# MB_RELAY.net
KiCad netlist of a schematic drawn in Altium Designer
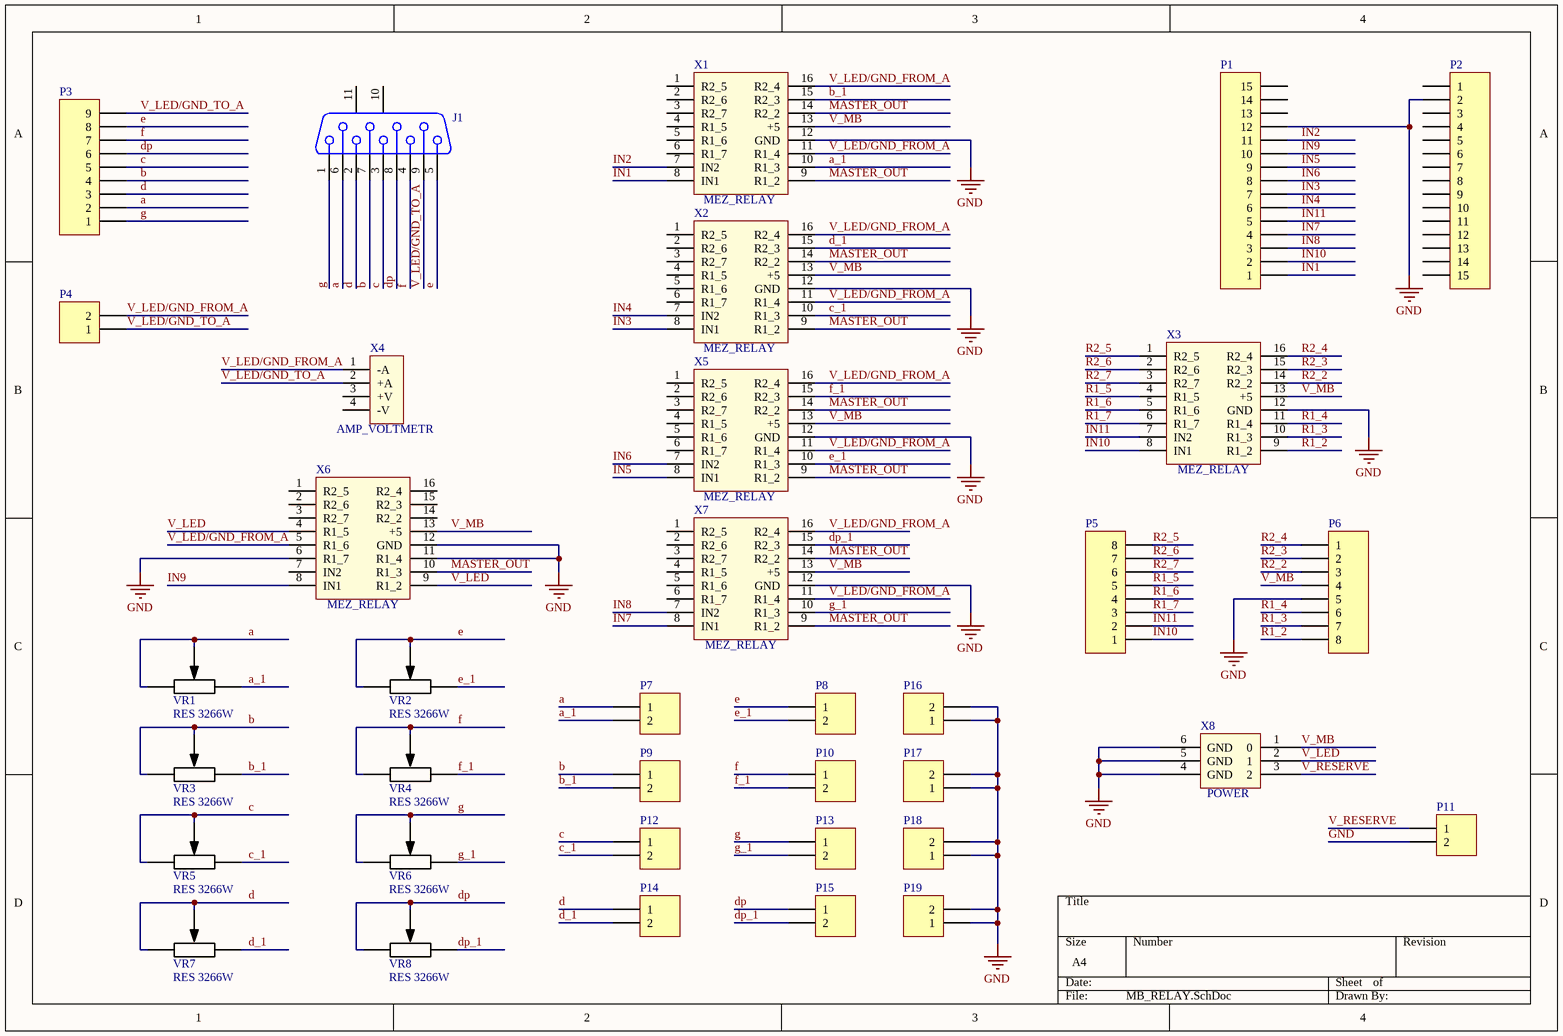
[diagram p0: MB_RELAY.SchDoc]

(export (version "E")
  (design (tool "Eeschema 10.0.6"))
  (components
    (comp (ref "J1")
      (value "D Connector 9")
      (footprint "DSUB1.385-2H9")
      (description "Receptacle Assembly, 9 Position, Right Angle")
      (fields (field (name "PUBLISHER") "Altium Limited"))
      (libsource (lib "Miscellaneous Connectors") (part "D Connector 9"))
    )
    (comp (ref "P1")
      (value "Header 15")
      (footprint "HDR1X15")
      (description "Header, 15-Pin")
      (fields (field (name "PUBLISHER") "Altium Limited"))
      (libsource (lib "Miscellaneous Connectors") (part "Header 15"))
    )
    (comp (ref "P2")
      (value "Header 15")
      (footprint "HDR1X15")
      (description "Header, 15-Pin")
      (fields (field (name "PUBLISHER") "Altium Limited"))
      (libsource (lib "") (part "Header 15_1"))
    )
    (comp (ref "P3")
      (value "Header 9")
      (footprint "HDR1X9")
      (description "Header, 9-Pin")
      (fields (field (name "PUBLISHER") "Altium Limited"))
      (libsource (lib "Miscellaneous Connectors") (part "Header 9"))
    )
    (comp (ref "P4")
      (value "Header 2")
      (footprint "HDR1X2")
      (description "Header, 2-Pin")
      (fields (field (name "PUBLISHER") "Altium Limited"))
      (libsource (lib "Miscellaneous Connectors") (part "Header 2"))
    )
    (comp (ref "P5")
      (value "Header 8")
      (footprint "HDR1X8")
      (description "Header, 8-Pin")
      (fields (field (name "PUBLISHER") "Altium Limited"))
      (libsource (lib "") (part "Header 8_1"))
    )
    (comp (ref "P6")
      (value "Header 8")
      (footprint "HDR1X8")
      (description "Header, 8-Pin")
      (fields (field (name "PUBLISHER") "Altium Limited"))
      (libsource (lib "Miscellaneous Connectors") (part "Header 8"))
    )
    (comp (ref "P7")
      (value "Header 2")
      (footprint "HDR1X2")
      (description "Header, 2-Pin")
      (fields (field (name "PUBLISHER") "Altium Limited"))
      (libsource (lib "") (part "Header 2_1"))
    )
    (comp (ref "P8")
      (value "GND")
      (footprint "HDR1X2")
      (description "Header, 2-Pin")
      (fields (field (name "PUBLISHER") "Altium Limited"))
      (libsource (lib "") (part "Header 2_1"))
    )
    (comp (ref "P9")
      (value "Header 2")
      (footprint "HDR1X2")
      (description "Header, 2-Pin")
      (fields (field (name "PUBLISHER") "Altium Limited"))
      (libsource (lib "") (part "Header 2_1"))
    )
    (comp (ref "P10")
      (value "GND")
      (footprint "HDR1X2")
      (description "Header, 2-Pin")
      (fields (field (name "PUBLISHER") "Altium Limited"))
      (libsource (lib "") (part "Header 2_1"))
    )
    (comp (ref "P11")
      (value "Header 2")
      (footprint "HDR1X2")
      (description "Header, 2-Pin")
      (fields (field (name "PUBLISHER") "Altium Limited"))
      (libsource (lib "") (part "Header 2_1"))
    )
    (comp (ref "P12")
      (value "Header 2")
      (footprint "HDR1X2")
      (description "Header, 2-Pin")
      (fields (field (name "PUBLISHER") "Altium Limited"))
      (libsource (lib "") (part "Header 2_1"))
    )
    (comp (ref "P13")
      (value "GND")
      (footprint "HDR1X2")
      (description "Header, 2-Pin")
      (fields (field (name "PUBLISHER") "Altium Limited"))
      (libsource (lib "") (part "Header 2_1"))
    )
    (comp (ref "P14")
      (value "Header 2")
      (footprint "HDR1X2")
      (description "Header, 2-Pin")
      (fields (field (name "PUBLISHER") "Altium Limited"))
      (libsource (lib "") (part "Header 2_1"))
    )
    (comp (ref "P15")
      (value "GND")
      (footprint "HDR1X2")
      (description "Header, 2-Pin")
      (fields (field (name "PUBLISHER") "Altium Limited"))
      (libsource (lib "") (part "Header 2_1"))
    )
    (comp (ref "P16")
      (value "GND")
      (footprint "HDR1X2")
      (description "Header, 2-Pin")
      (fields (field (name "PUBLISHER") "Altium Limited"))
      (libsource (lib "Miscellaneous Connectors") (part "Header 2"))
    )
    (comp (ref "P17")
      (value "GND")
      (footprint "HDR1X2")
      (description "Header, 2-Pin")
      (fields (field (name "PUBLISHER") "Altium Limited"))
      (libsource (lib "Miscellaneous Connectors") (part "Header 2"))
    )
    (comp (ref "P18")
      (value "GND")
      (footprint "HDR1X2")
      (description "Header, 2-Pin")
      (fields (field (name "PUBLISHER") "Altium Limited"))
      (libsource (lib "Miscellaneous Connectors") (part "Header 2"))
    )
    (comp (ref "P19")
      (value "GND")
      (footprint "HDR1X2")
      (description "Header, 2-Pin")
      (fields (field (name "PUBLISHER") "Altium Limited"))
      (libsource (lib "Miscellaneous Connectors") (part "Header 2"))
    )
    (comp (ref "VR1")
      (value "RES 3266W")
      (footprint "aab_Passive:RES 3266W")
      (libsource (lib "aab_Schlib") (part "RES 3266W"))
    )
    (comp (ref "VR2")
      (value "RES 3266W")
      (footprint "aab_Passive:RES 3266W")
      (libsource (lib "aab_Schlib") (part "RES 3266W"))
    )
    (comp (ref "VR3")
      (value "RES 3266W")
      (footprint "aab_Passive:RES 3266W")
      (libsource (lib "aab_Schlib") (part "RES 3266W"))
    )
    (comp (ref "VR4")
      (value "RES 3266W")
      (footprint "aab_Passive:RES 3266W")
      (libsource (lib "aab_Schlib") (part "RES 3266W"))
    )
    (comp (ref "VR5")
      (value "RES 3266W")
      (footprint "aab_Passive:RES 3266W")
      (libsource (lib "aab_Schlib") (part "RES 3266W"))
    )
    (comp (ref "VR6")
      (value "RES 3266W")
      (footprint "aab_Passive:RES 3266W")
      (libsource (lib "aab_Schlib") (part "RES 3266W"))
    )
    (comp (ref "VR7")
      (value "RES 3266W")
      (footprint "aab_Passive:RES 3266W")
      (libsource (lib "aab_Schlib") (part "RES 3266W"))
    )
    (comp (ref "VR8")
      (value "RES 3266W")
      (footprint "aab_Passive:RES 3266W")
      (libsource (lib "aab_Schlib") (part "RES 3266W"))
    )
    (comp (ref "X1")
      (value "MEZ_RELAY")
      (footprint "MEZ_RELAY")
      (libsource (lib "msp_SchLib") (part "MEZ_RELAY"))
    )
    (comp (ref "X2")
      (value "MEZ_RELAY")
      (footprint "MEZ_RELAY")
      (libsource (lib "msp_SchLib") (part "MEZ_RELAY"))
    )
    (comp (ref "X3")
      (value "MEZ_RELAY")
      (footprint "MEZ_RELAY")
      (libsource (lib "msp_SchLib") (part "MEZ_RELAY"))
    )
    (comp (ref "X4")
      (value "AMP_VOLTMETR")
      (footprint "vpl_Passive:AMP_VOLTMETER")
      (libsource (lib "msp_SchLib") (part "AMP_VOLTMETR"))
    )
    (comp (ref "X5")
      (value "MEZ_RELAY")
      (footprint "MEZ_RELAY")
      (libsource (lib "msp_SchLib") (part "MEZ_RELAY"))
    )
    (comp (ref "X6")
      (value "MEZ_RELAY")
      (footprint "MEZ_RELAY")
      (libsource (lib "msp_SchLib") (part "MEZ_RELAY"))
    )
    (comp (ref "X7")
      (value "MEZ_RELAY")
      (footprint "MEZ_RELAY")
      (libsource (lib "msp_SchLib") (part "MEZ_RELAY"))
    )
    (comp (ref "X8")
      (value "POWER")
      (footprint "vpl_Passive:POWER")
      (libsource (lib "msp_SchLib") (part "POWER"))
    )
  )
  (nets
    (net (code "1") (name "/IN1") (class "Default")
      (node (ref "P1") (pin "1") (pinfunction "1_1") (pintype "passive"))
      (node (ref "X1") (pin "8") (pinfunction "IN1_8") (pintype "passive"))
    )
    (net (code "2") (name "/IN2") (class "Default")
      (node (ref "P1") (pin "11") (pinfunction "11_11") (pintype "passive"))
      (node (ref "X1") (pin "7") (pinfunction "IN2_7") (pintype "passive"))
    )
    (net (code "3") (name "/IN3") (class "Default")
      (node (ref "P1") (pin "7") (pinfunction "7_7") (pintype "passive"))
      (node (ref "X2") (pin "8") (pinfunction "IN1_8") (pintype "passive"))
    )
    (net (code "4") (name "/IN4") (class "Default")
      (node (ref "P1") (pin "6") (pinfunction "6_6") (pintype "passive"))
      (node (ref "X2") (pin "7") (pinfunction "IN2_7") (pintype "passive"))
    )
    (net (code "5") (name "/IN5") (class "Default")
      (node (ref "P1") (pin "9") (pinfunction "9_9") (pintype "passive"))
      (node (ref "X5") (pin "8") (pinfunction "IN1_8") (pintype "passive"))
    )
    (net (code "6") (name "/IN6") (class "Default")
      (node (ref "P1") (pin "8") (pinfunction "8_8") (pintype "passive"))
      (node (ref "X5") (pin "7") (pinfunction "IN2_7") (pintype "passive"))
    )
    (net (code "7") (name "/IN7") (class "Default")
      (node (ref "P1") (pin "4") (pinfunction "4_4") (pintype "passive"))
      (node (ref "X7") (pin "8") (pinfunction "IN1_8") (pintype "passive"))
    )
    (net (code "8") (name "/IN8") (class "Default")
      (node (ref "P1") (pin "3") (pinfunction "3_3") (pintype "passive"))
      (node (ref "X7") (pin "7") (pinfunction "IN2_7") (pintype "passive"))
    )
    (net (code "9") (name "/IN9") (class "Default")
      (node (ref "P1") (pin "10") (pinfunction "10_10") (pintype "passive"))
      (node (ref "X6") (pin "8") (pinfunction "IN1_8") (pintype "passive"))
    )
    (net (code "10") (name "/IN10") (class "Default")
      (node (ref "P1") (pin "2") (pinfunction "2_2") (pintype "passive"))
      (node (ref "P5") (pin "1") (pinfunction "1_1") (pintype "passive"))
      (node (ref "X3") (pin "8") (pinfunction "IN1_8") (pintype "passive"))
    )
    (net (code "11") (name "/IN11") (class "Default")
      (node (ref "P1") (pin "5") (pinfunction "5_5") (pintype "passive"))
      (node (ref "P5") (pin "2") (pinfunction "2_2") (pintype "passive"))
      (node (ref "X3") (pin "7") (pinfunction "IN2_7") (pintype "passive"))
    )
    (net (code "12") (name "/MASTER_OUT") (class "Default")
      (node (ref "X1") (pin "14") (pinfunction "R2_2_14") (pintype "passive"))
      (node (ref "X1") (pin "9") (pinfunction "R1_2_9") (pintype "passive"))
      (node (ref "X2") (pin "14") (pinfunction "R2_2_14") (pintype "passive"))
      (node (ref "X2") (pin "9") (pinfunction "R1_2_9") (pintype "passive"))
      (node (ref "X5") (pin "14") (pinfunction "R2_2_14") (pintype "passive"))
      (node (ref "X5") (pin "9") (pinfunction "R1_2_9") (pintype "passive"))
      (node (ref "X6") (pin "10") (pinfunction "R1_3_10") (pintype "passive"))
      (node (ref "X7") (pin "14") (pinfunction "R2_2_14") (pintype "passive"))
      (node (ref "X7") (pin "9") (pinfunction "R1_2_9") (pintype "passive"))
    )
    (net (code "13") (name "/R1_2") (class "Default")
      (node (ref "P6") (pin "8") (pinfunction "8_8") (pintype "passive"))
      (node (ref "X3") (pin "9") (pinfunction "R1_2_9") (pintype "passive"))
    )
    (net (code "14") (name "/R1_3") (class "Default")
      (node (ref "P6") (pin "7") (pinfunction "7_7") (pintype "passive"))
      (node (ref "X3") (pin "10") (pinfunction "R1_3_10") (pintype "passive"))
    )
    (net (code "15") (name "/R1_4") (class "Default")
      (node (ref "P6") (pin "6") (pinfunction "6_6") (pintype "passive"))
      (node (ref "X3") (pin "11") (pinfunction "R1_4_11") (pintype "passive"))
    )
    (net (code "16") (name "/R1_5") (class "Default")
      (node (ref "P5") (pin "5") (pinfunction "5_5") (pintype "passive"))
      (node (ref "X3") (pin "4") (pinfunction "R1_5_4") (pintype "passive"))
    )
    (net (code "17") (name "/R1_6") (class "Default")
      (node (ref "P5") (pin "4") (pinfunction "4_4") (pintype "passive"))
      (node (ref "X3") (pin "5") (pinfunction "R1_6_5") (pintype "passive"))
    )
    (net (code "18") (name "/R1_7") (class "Default")
      (node (ref "P5") (pin "3") (pinfunction "3_3") (pintype "passive"))
      (node (ref "X3") (pin "6") (pinfunction "R1_7_6") (pintype "passive"))
    )
    (net (code "19") (name "/R2_2") (class "Default")
      (node (ref "P6") (pin "3") (pinfunction "3_3") (pintype "passive"))
      (node (ref "X3") (pin "14") (pinfunction "R2_2_14") (pintype "passive"))
    )
    (net (code "20") (name "/R2_3") (class "Default")
      (node (ref "P6") (pin "2") (pinfunction "2_2") (pintype "passive"))
      (node (ref "X3") (pin "15") (pinfunction "R2_3_15") (pintype "passive"))
    )
    (net (code "21") (name "/R2_4") (class "Default")
      (node (ref "P6") (pin "1") (pinfunction "1_1") (pintype "passive"))
      (node (ref "X3") (pin "16") (pinfunction "R2_4_16") (pintype "passive"))
    )
    (net (code "22") (name "/R2_5") (class "Default")
      (node (ref "P5") (pin "8") (pinfunction "8_8") (pintype "passive"))
      (node (ref "X3") (pin "1") (pinfunction "R2_5_1") (pintype "passive"))
    )
    (net (code "23") (name "/R2_6") (class "Default")
      (node (ref "P5") (pin "7") (pinfunction "7_7") (pintype "passive"))
      (node (ref "X3") (pin "2") (pinfunction "R2_6_2") (pintype "passive"))
    )
    (net (code "24") (name "/R2_7") (class "Default")
      (node (ref "P5") (pin "6") (pinfunction "6_6") (pintype "passive"))
      (node (ref "X3") (pin "3") (pinfunction "R2_7_3") (pintype "passive"))
    )
    (net (code "25") (name "/V_LED") (class "Default")
      (node (ref "X6") (pin "4") (pinfunction "R1_5_4") (pintype "passive"))
      (node (ref "X6") (pin "9") (pinfunction "R1_2_9") (pintype "passive"))
      (node (ref "X8") (pin "2") (pinfunction "1_2") (pintype "passive"))
    )
    (net (code "26") (name "/V_LED{slash}GND_FROM_A") (class "Default")
      (node (ref "P4") (pin "2") (pinfunction "2_2") (pintype "passive"))
      (node (ref "X1") (pin "11") (pinfunction "R1_4_11") (pintype "passive"))
      (node (ref "X1") (pin "16") (pinfunction "R2_4_16") (pintype "passive"))
      (node (ref "X2") (pin "11") (pinfunction "R1_4_11") (pintype "passive"))
      (node (ref "X2") (pin "16") (pinfunction "R2_4_16") (pintype "passive"))
      (node (ref "X4") (pin "1") (pinfunction "-A_1") (pintype "passive"))
      (node (ref "X5") (pin "11") (pinfunction "R1_4_11") (pintype "passive"))
      (node (ref "X5") (pin "16") (pinfunction "R2_4_16") (pintype "passive"))
      (node (ref "X6") (pin "5") (pinfunction "R1_6_5") (pintype "passive"))
      (node (ref "X7") (pin "11") (pinfunction "R1_4_11") (pintype "passive"))
      (node (ref "X7") (pin "16") (pinfunction "R2_4_16") (pintype "passive"))
    )
    (net (code "27") (name "/V_LED{slash}GND_TO_A") (class "Default")
      (node (ref "J1") (pin "9") (pinfunction "9_9") (pintype "passive"))
      (node (ref "P3") (pin "9") (pinfunction "9_9") (pintype "passive"))
      (node (ref "P4") (pin "1") (pinfunction "1_1") (pintype "passive"))
      (node (ref "X4") (pin "2") (pinfunction "+A_2") (pintype "passive"))
    )
    (net (code "28") (name "/V_MB") (class "Default")
      (node (ref "P6") (pin "4") (pinfunction "4_4") (pintype "passive"))
      (node (ref "X1") (pin "13") (pinfunction "+5_13") (pintype "passive"))
      (node (ref "X2") (pin "13") (pinfunction "+5_13") (pintype "passive"))
      (node (ref "X3") (pin "13") (pinfunction "+5_13") (pintype "passive"))
      (node (ref "X5") (pin "13") (pinfunction "+5_13") (pintype "passive"))
      (node (ref "X6") (pin "13") (pinfunction "+5_13") (pintype "passive"))
      (node (ref "X7") (pin "13") (pinfunction "+5_13") (pintype "passive"))
      (node (ref "X8") (pin "1") (pinfunction "0_1") (pintype "passive"))
    )
    (net (code "29") (name "/V_RESERVE") (class "Default")
      (node (ref "P11") (pin "1") (pinfunction "1_1") (pintype "passive"))
      (node (ref "X8") (pin "3") (pinfunction "2_3") (pintype "passive"))
    )
    (net (code "30") (name "/a") (class "Default")
      (node (ref "J1") (pin "6") (pinfunction "6_6") (pintype "passive"))
      (node (ref "P3") (pin "2") (pinfunction "2_2") (pintype "passive"))
      (node (ref "P7") (pin "1") (pinfunction "1_1") (pintype "passive"))
      (node (ref "VR1") (pin "1") (pinfunction "1_1") (pintype "passive"))
      (node (ref "VR1") (pin "2") (pinfunction "2_2") (pintype "passive"))
    )
    (net (code "31") (name "/a_1") (class "Default")
      (node (ref "P7") (pin "2") (pinfunction "2_2") (pintype "passive"))
      (node (ref "VR1") (pin "3") (pinfunction "3_3") (pintype "passive"))
      (node (ref "X1") (pin "10") (pinfunction "R1_3_10") (pintype "passive"))
    )
    (net (code "32") (name "/b") (class "Default")
      (node (ref "J1") (pin "7") (pinfunction "7_7") (pintype "passive"))
      (node (ref "P3") (pin "4") (pinfunction "4_4") (pintype "passive"))
      (node (ref "P9") (pin "1") (pinfunction "1_1") (pintype "passive"))
      (node (ref "VR3") (pin "1") (pinfunction "1_1") (pintype "passive"))
      (node (ref "VR3") (pin "2") (pinfunction "2_2") (pintype "passive"))
    )
    (net (code "33") (name "/b_1") (class "Default")
      (node (ref "P9") (pin "2") (pinfunction "2_2") (pintype "passive"))
      (node (ref "VR3") (pin "3") (pinfunction "3_3") (pintype "passive"))
      (node (ref "X1") (pin "15") (pinfunction "R2_3_15") (pintype "passive"))
    )
    (net (code "34") (name "/c") (class "Default")
      (node (ref "J1") (pin "3") (pinfunction "3_3") (pintype "passive"))
      (node (ref "P12") (pin "1") (pinfunction "1_1") (pintype "passive"))
      (node (ref "P3") (pin "5") (pinfunction "5_5") (pintype "passive"))
      (node (ref "VR5") (pin "1") (pinfunction "1_1") (pintype "passive"))
      (node (ref "VR5") (pin "2") (pinfunction "2_2") (pintype "passive"))
    )
    (net (code "35") (name "/c_1") (class "Default")
      (node (ref "P12") (pin "2") (pinfunction "2_2") (pintype "passive"))
      (node (ref "VR5") (pin "3") (pinfunction "3_3") (pintype "passive"))
      (node (ref "X2") (pin "10") (pinfunction "R1_3_10") (pintype "passive"))
    )
    (net (code "36") (name "/d") (class "Default")
      (node (ref "J1") (pin "2") (pinfunction "2_2") (pintype "passive"))
      (node (ref "P14") (pin "1") (pinfunction "1_1") (pintype "passive"))
      (node (ref "P3") (pin "3") (pinfunction "3_3") (pintype "passive"))
      (node (ref "VR7") (pin "1") (pinfunction "1_1") (pintype "passive"))
      (node (ref "VR7") (pin "2") (pinfunction "2_2") (pintype "passive"))
    )
    (net (code "37") (name "/d_1") (class "Default")
      (node (ref "P14") (pin "2") (pinfunction "2_2") (pintype "passive"))
      (node (ref "VR7") (pin "3") (pinfunction "3_3") (pintype "passive"))
      (node (ref "X2") (pin "15") (pinfunction "R2_3_15") (pintype "passive"))
    )
    (net (code "38") (name "/dp") (class "Default")
      (node (ref "J1") (pin "8") (pinfunction "8_8") (pintype "passive"))
      (node (ref "P15") (pin "1") (pinfunction "1_1") (pintype "passive"))
      (node (ref "P3") (pin "6") (pinfunction "6_6") (pintype "passive"))
      (node (ref "VR8") (pin "1") (pinfunction "1_1") (pintype "passive"))
      (node (ref "VR8") (pin "2") (pinfunction "2_2") (pintype "passive"))
    )
    (net (code "39") (name "/dp_1") (class "Default")
      (node (ref "P15") (pin "2") (pinfunction "2_2") (pintype "passive"))
      (node (ref "VR8") (pin "3") (pinfunction "3_3") (pintype "passive"))
      (node (ref "X7") (pin "15") (pinfunction "R2_3_15") (pintype "passive"))
    )
    (net (code "40") (name "/e") (class "Default")
      (node (ref "J1") (pin "5") (pinfunction "5_5") (pintype "passive"))
      (node (ref "P3") (pin "8") (pinfunction "8_8") (pintype "passive"))
      (node (ref "P8") (pin "1") (pinfunction "1_1") (pintype "passive"))
      (node (ref "VR2") (pin "1") (pinfunction "1_1") (pintype "passive"))
      (node (ref "VR2") (pin "2") (pinfunction "2_2") (pintype "passive"))
    )
    (net (code "41") (name "/e_1") (class "Default")
      (node (ref "P8") (pin "2") (pinfunction "2_2") (pintype "passive"))
      (node (ref "VR2") (pin "3") (pinfunction "3_3") (pintype "passive"))
      (node (ref "X5") (pin "10") (pinfunction "R1_3_10") (pintype "passive"))
    )
    (net (code "42") (name "/f") (class "Default")
      (node (ref "J1") (pin "4") (pinfunction "4_4") (pintype "passive"))
      (node (ref "P10") (pin "1") (pinfunction "1_1") (pintype "passive"))
      (node (ref "P3") (pin "7") (pinfunction "7_7") (pintype "passive"))
      (node (ref "VR4") (pin "1") (pinfunction "1_1") (pintype "passive"))
      (node (ref "VR4") (pin "2") (pinfunction "2_2") (pintype "passive"))
    )
    (net (code "43") (name "/f_1") (class "Default")
      (node (ref "P10") (pin "2") (pinfunction "2_2") (pintype "passive"))
      (node (ref "VR4") (pin "3") (pinfunction "3_3") (pintype "passive"))
      (node (ref "X5") (pin "15") (pinfunction "R2_3_15") (pintype "passive"))
    )
    (net (code "44") (name "/g") (class "Default")
      (node (ref "J1") (pin "1") (pinfunction "1_1") (pintype "passive"))
      (node (ref "P13") (pin "1") (pinfunction "1_1") (pintype "passive"))
      (node (ref "P3") (pin "1") (pinfunction "1_1") (pintype "passive"))
      (node (ref "VR6") (pin "1") (pinfunction "1_1") (pintype "passive"))
      (node (ref "VR6") (pin "2") (pinfunction "2_2") (pintype "passive"))
    )
    (net (code "45") (name "/g_1") (class "Default")
      (node (ref "P13") (pin "2") (pinfunction "2_2") (pintype "passive"))
      (node (ref "VR6") (pin "3") (pinfunction "3_3") (pintype "passive"))
      (node (ref "X7") (pin "10") (pinfunction "R1_3_10") (pintype "passive"))
    )
    (net (code "46") (name "GND") (class "Default")
      (node (ref "P1") (pin "12") (pinfunction "12_12") (pintype "passive"))
      (node (ref "P11") (pin "2") (pinfunction "2_2") (pintype "passive"))
      (node (ref "P16") (pin "1") (pinfunction "1_1") (pintype "passive"))
      (node (ref "P16") (pin "2") (pinfunction "2_2") (pintype "passive"))
      (node (ref "P17") (pin "1") (pinfunction "1_1") (pintype "passive"))
      (node (ref "P17") (pin "2") (pinfunction "2_2") (pintype "passive"))
      (node (ref "P18") (pin "1") (pinfunction "1_1") (pintype "passive"))
      (node (ref "P18") (pin "2") (pinfunction "2_2") (pintype "passive"))
      (node (ref "P19") (pin "1") (pinfunction "1_1") (pintype "passive"))
      (node (ref "P19") (pin "2") (pinfunction "2_2") (pintype "passive"))
      (node (ref "P2") (pin "2") (pinfunction "2_2") (pintype "passive"))
      (node (ref "P6") (pin "5") (pinfunction "5_5") (pintype "passive"))
      (node (ref "X1") (pin "12") (pinfunction "GND_12") (pintype "passive"))
      (node (ref "X2") (pin "12") (pinfunction "GND_12") (pintype "passive"))
      (node (ref "X3") (pin "12") (pinfunction "GND_12") (pintype "passive"))
      (node (ref "X5") (pin "12") (pinfunction "GND_12") (pintype "passive"))
      (node (ref "X6") (pin "11") (pinfunction "R1_4_11") (pintype "passive"))
      (node (ref "X6") (pin "12") (pinfunction "GND_12") (pintype "passive"))
      (node (ref "X6") (pin "6") (pinfunction "R1_7_6") (pintype "passive"))
      (node (ref "X7") (pin "12") (pinfunction "GND_12") (pintype "passive"))
      (node (ref "X8") (pin "4") (pinfunction "GND_4") (pintype "passive"))
      (node (ref "X8") (pin "5") (pinfunction "GND_5") (pintype "passive"))
      (node (ref "X8") (pin "6") (pinfunction "GND_6") (pintype "passive"))
    )
    (net (code "47") (name "unconnected-(J1-MH1-Pad10)") (class "Default")
      (node (ref "J1") (pin "10") (pinfunction "MH1_10") (pintype "passive"))
    )
    (net (code "48") (name "unconnected-(J1-MH2-Pad11)") (class "Default")
      (node (ref "J1") (pin "11") (pinfunction "MH2_11") (pintype "passive"))
    )
    (net (code "49") (name "unconnected-(P1-Pad13)") (class "Default")
      (node (ref "P1") (pin "13") (pinfunction "13_13") (pintype "passive"))
    )
    (net (code "50") (name "unconnected-(P1-Pad14)") (class "Default")
      (node (ref "P1") (pin "14") (pinfunction "14_14") (pintype "passive"))
    )
    (net (code "51") (name "unconnected-(P1-Pad15)") (class "Default")
      (node (ref "P1") (pin "15") (pinfunction "15_15") (pintype "passive"))
    )
    (net (code "52") (name "unconnected-(P2-Pad1)") (class "Default")
      (node (ref "P2") (pin "1") (pinfunction "1_1") (pintype "passive"))
    )
    (net (code "53") (name "unconnected-(P2-Pad3)") (class "Default")
      (node (ref "P2") (pin "3") (pinfunction "3_3") (pintype "passive"))
    )
    (net (code "54") (name "unconnected-(P2-Pad4)") (class "Default")
      (node (ref "P2") (pin "4") (pinfunction "4_4") (pintype "passive"))
    )
    (net (code "55") (name "unconnected-(P2-Pad5)") (class "Default")
      (node (ref "P2") (pin "5") (pinfunction "5_5") (pintype "passive"))
    )
    (net (code "56") (name "unconnected-(P2-Pad6)") (class "Default")
      (node (ref "P2") (pin "6") (pinfunction "6_6") (pintype "passive"))
    )
    (net (code "57") (name "unconnected-(P2-Pad7)") (class "Default")
      (node (ref "P2") (pin "7") (pinfunction "7_7") (pintype "passive"))
    )
    (net (code "58") (name "unconnected-(P2-Pad8)") (class "Default")
      (node (ref "P2") (pin "8") (pinfunction "8_8") (pintype "passive"))
    )
    (net (code "59") (name "unconnected-(P2-Pad9)") (class "Default")
      (node (ref "P2") (pin "9") (pinfunction "9_9") (pintype "passive"))
    )
    (net (code "60") (name "unconnected-(P2-Pad10)") (class "Default")
      (node (ref "P2") (pin "10") (pinfunction "10_10") (pintype "passive"))
    )
    (net (code "61") (name "unconnected-(P2-Pad11)") (class "Default")
      (node (ref "P2") (pin "11") (pinfunction "11_11") (pintype "passive"))
    )
    (net (code "62") (name "unconnected-(P2-Pad12)") (class "Default")
      (node (ref "P2") (pin "12") (pinfunction "12_12") (pintype "passive"))
    )
    (net (code "63") (name "unconnected-(P2-Pad13)") (class "Default")
      (node (ref "P2") (pin "13") (pinfunction "13_13") (pintype "passive"))
    )
    (net (code "64") (name "unconnected-(P2-Pad14)") (class "Default")
      (node (ref "P2") (pin "14") (pinfunction "14_14") (pintype "passive"))
    )
    (net (code "65") (name "unconnected-(P2-Pad15)") (class "Default")
      (node (ref "P2") (pin "15") (pinfunction "15_15") (pintype "passive"))
    )
    (net (code "66") (name "unconnected-(X1-R1_5-Pad4)") (class "Default")
      (node (ref "X1") (pin "4") (pinfunction "R1_5_4") (pintype "passive"))
    )
    (net (code "67") (name "unconnected-(X1-R1_6-Pad5)") (class "Default")
      (node (ref "X1") (pin "5") (pinfunction "R1_6_5") (pintype "passive"))
    )
    (net (code "68") (name "unconnected-(X1-R1_7-Pad6)") (class "Default")
      (node (ref "X1") (pin "6") (pinfunction "R1_7_6") (pintype "passive"))
    )
    (net (code "69") (name "unconnected-(X1-R2_5-Pad1)") (class "Default")
      (node (ref "X1") (pin "1") (pinfunction "R2_5_1") (pintype "passive"))
    )
    (net (code "70") (name "unconnected-(X1-R2_6-Pad2)") (class "Default")
      (node (ref "X1") (pin "2") (pinfunction "R2_6_2") (pintype "passive"))
    )
    (net (code "71") (name "unconnected-(X1-R2_7-Pad3)") (class "Default")
      (node (ref "X1") (pin "3") (pinfunction "R2_7_3") (pintype "passive"))
    )
    (net (code "72") (name "unconnected-(X2-R1_5-Pad4)") (class "Default")
      (node (ref "X2") (pin "4") (pinfunction "R1_5_4") (pintype "passive"))
    )
    (net (code "73") (name "unconnected-(X2-R1_6-Pad5)") (class "Default")
      (node (ref "X2") (pin "5") (pinfunction "R1_6_5") (pintype "passive"))
    )
    (net (code "74") (name "unconnected-(X2-R1_7-Pad6)") (class "Default")
      (node (ref "X2") (pin "6") (pinfunction "R1_7_6") (pintype "passive"))
    )
    (net (code "75") (name "unconnected-(X2-R2_5-Pad1)") (class "Default")
      (node (ref "X2") (pin "1") (pinfunction "R2_5_1") (pintype "passive"))
    )
    (net (code "76") (name "unconnected-(X2-R2_6-Pad2)") (class "Default")
      (node (ref "X2") (pin "2") (pinfunction "R2_6_2") (pintype "passive"))
    )
    (net (code "77") (name "unconnected-(X2-R2_7-Pad3)") (class "Default")
      (node (ref "X2") (pin "3") (pinfunction "R2_7_3") (pintype "passive"))
    )
    (net (code "78") (name "unconnected-(X4-+V-Pad3)") (class "Default")
      (node (ref "X4") (pin "3") (pinfunction "+V_3") (pintype "passive"))
    )
    (net (code "79") (name "unconnected-(X4--V-Pad4)") (class "Default")
      (node (ref "X4") (pin "4") (pinfunction "-V_4") (pintype "passive"))
    )
    (net (code "80") (name "unconnected-(X5-R1_5-Pad4)") (class "Default")
      (node (ref "X5") (pin "4") (pinfunction "R1_5_4") (pintype "passive"))
    )
    (net (code "81") (name "unconnected-(X5-R1_6-Pad5)") (class "Default")
      (node (ref "X5") (pin "5") (pinfunction "R1_6_5") (pintype "passive"))
    )
    (net (code "82") (name "unconnected-(X5-R1_7-Pad6)") (class "Default")
      (node (ref "X5") (pin "6") (pinfunction "R1_7_6") (pintype "passive"))
    )
    (net (code "83") (name "unconnected-(X5-R2_5-Pad1)") (class "Default")
      (node (ref "X5") (pin "1") (pinfunction "R2_5_1") (pintype "passive"))
    )
    (net (code "84") (name "unconnected-(X5-R2_6-Pad2)") (class "Default")
      (node (ref "X5") (pin "2") (pinfunction "R2_6_2") (pintype "passive"))
    )
    (net (code "85") (name "unconnected-(X5-R2_7-Pad3)") (class "Default")
      (node (ref "X5") (pin "3") (pinfunction "R2_7_3") (pintype "passive"))
    )
    (net (code "86") (name "unconnected-(X6-IN2-Pad7)") (class "Default")
      (node (ref "X6") (pin "7") (pinfunction "IN2_7") (pintype "passive"))
    )
    (net (code "87") (name "unconnected-(X6-R2_2-Pad14)") (class "Default")
      (node (ref "X6") (pin "14") (pinfunction "R2_2_14") (pintype "passive"))
    )
    (net (code "88") (name "unconnected-(X6-R2_3-Pad15)") (class "Default")
      (node (ref "X6") (pin "15") (pinfunction "R2_3_15") (pintype "passive"))
    )
    (net (code "89") (name "unconnected-(X6-R2_4-Pad16)") (class "Default")
      (node (ref "X6") (pin "16") (pinfunction "R2_4_16") (pintype "passive"))
    )
    (net (code "90") (name "unconnected-(X6-R2_5-Pad1)") (class "Default")
      (node (ref "X6") (pin "1") (pinfunction "R2_5_1") (pintype "passive"))
    )
    (net (code "91") (name "unconnected-(X6-R2_6-Pad2)") (class "Default")
      (node (ref "X6") (pin "2") (pinfunction "R2_6_2") (pintype "passive"))
    )
    (net (code "92") (name "unconnected-(X6-R2_7-Pad3)") (class "Default")
      (node (ref "X6") (pin "3") (pinfunction "R2_7_3") (pintype "passive"))
    )
    (net (code "93") (name "unconnected-(X7-R1_5-Pad4)") (class "Default")
      (node (ref "X7") (pin "4") (pinfunction "R1_5_4") (pintype "passive"))
    )
    (net (code "94") (name "unconnected-(X7-R1_6-Pad5)") (class "Default")
      (node (ref "X7") (pin "5") (pinfunction "R1_6_5") (pintype "passive"))
    )
    (net (code "95") (name "unconnected-(X7-R1_7-Pad6)") (class "Default")
      (node (ref "X7") (pin "6") (pinfunction "R1_7_6") (pintype "passive"))
    )
    (net (code "96") (name "unconnected-(X7-R2_5-Pad1)") (class "Default")
      (node (ref "X7") (pin "1") (pinfunction "R2_5_1") (pintype "passive"))
    )
    (net (code "97") (name "unconnected-(X7-R2_6-Pad2)") (class "Default")
      (node (ref "X7") (pin "2") (pinfunction "R2_6_2") (pintype "passive"))
    )
    (net (code "98") (name "unconnected-(X7-R2_7-Pad3)") (class "Default")
      (node (ref "X7") (pin "3") (pinfunction "R2_7_3") (pintype "passive"))
    )
  )
)
